# 2020can_master_v4_x.net
KiCad netlist of a schematic drawn in EAGLE
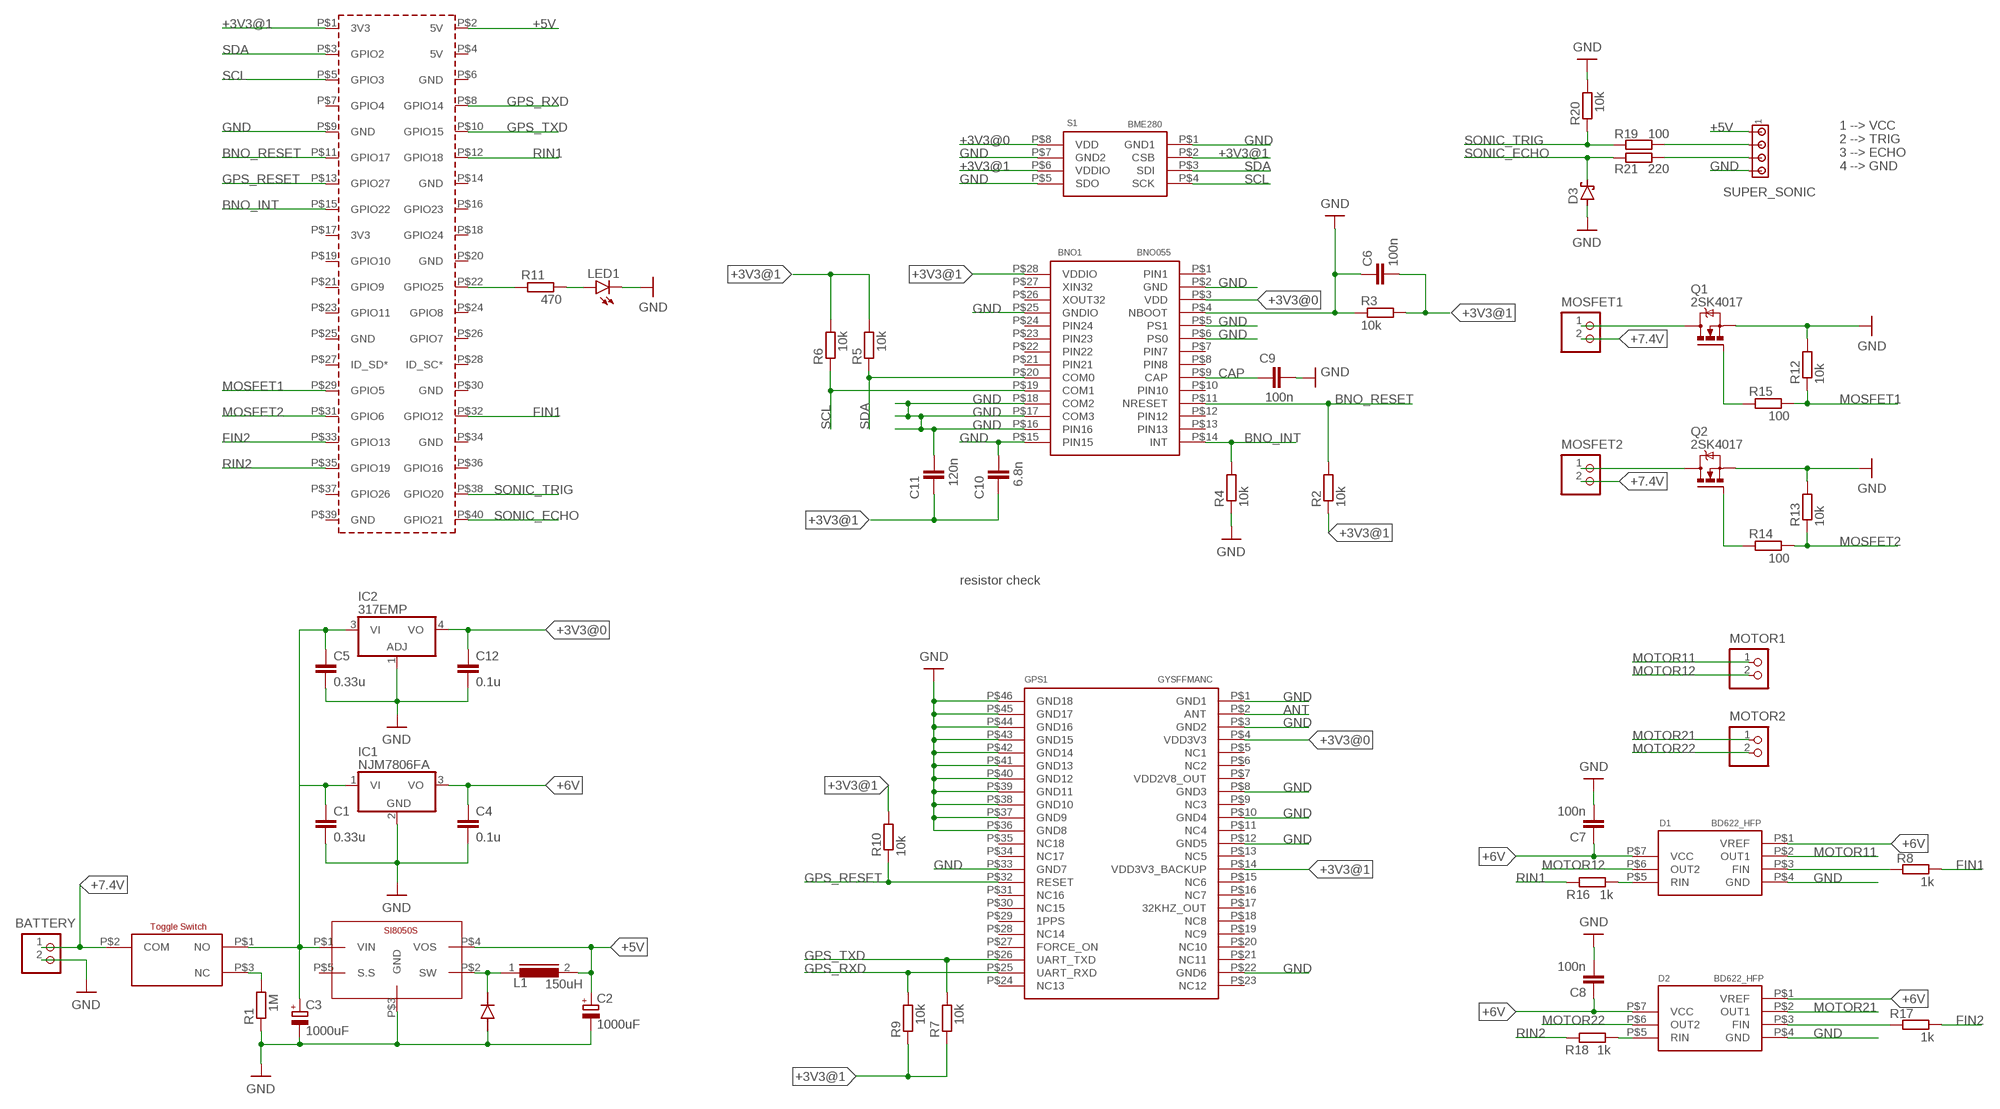
[diagram p0: schematic, sheet 1]

(export (version "E")
  (design (tool "Eeschema 10.0.6"))
  (components
    (comp (ref "BATTERY")
      (value "B2P-VH")
      (footprint "eagle-import:B2P-VH")
      (libsource (lib "eagle-import") (part "B2P-VH"))
    )
    (comp (ref "BNO1")
      (value "BNO055")
      (footprint "eagle-import:BNO055")
      (libsource (lib "eagle-import") (part "BNO055"))
    )
    (comp (ref "C1")
      (value "0.33u")
      (footprint "eagle-import:C5B3")
      (libsource (lib "eagle-import") (part "C5/3"))
    )
    (comp (ref "C2")
      (value "1000uF")
      (footprint "eagle-import:E5-10,5")
      (libsource (lib "eagle-import") (part "CPOL-EUE5-10.5"))
    )
    (comp (ref "C3")
      (value "1000uF")
      (footprint "eagle-import:E5-10,5")
      (libsource (lib "eagle-import") (part "CPOL-EUE5-10.5"))
    )
    (comp (ref "C4")
      (value "0.1u")
      (footprint "eagle-import:C5B3")
      (libsource (lib "eagle-import") (part "C5/3"))
    )
    (comp (ref "C5")
      (value "0.33u")
      (footprint "eagle-import:C5B3")
      (libsource (lib "eagle-import") (part "C5/3"))
    )
    (comp (ref "C6")
      (value "100n")
      (footprint "eagle-import:C1206")
      (libsource (lib "eagle-import") (part "C-EUC1206"))
    )
    (comp (ref "C7")
      (value "100n")
      (footprint "eagle-import:C1206")
      (libsource (lib "eagle-import") (part "C-EUC1206"))
    )
    (comp (ref "C8")
      (value "100n")
      (footprint "eagle-import:C1206")
      (libsource (lib "eagle-import") (part "C-EUC1206"))
    )
    (comp (ref "C9")
      (value "100n")
      (footprint "eagle-import:C1206")
      (libsource (lib "eagle-import") (part "C-EUC1206"))
    )
    (comp (ref "C10")
      (value "6.8n")
      (footprint "eagle-import:C1206")
      (libsource (lib "eagle-import") (part "C-EUC1206"))
    )
    (comp (ref "C11")
      (value "120n")
      (footprint "eagle-import:C1206")
      (libsource (lib "eagle-import") (part "C-EUC1206"))
    )
    (comp (ref "C12")
      (value "0.1u")
      (footprint "eagle-import:C5B3")
      (libsource (lib "eagle-import") (part "C5/3"))
    )
    (comp (ref "D1")
      (value "BD622_HFP")
      (footprint "eagle-import:BD62___HRP7")
      (libsource (lib "eagle-import") (part "BD622_HFP"))
    )
    (comp (ref "D2")
      (value "BD622_HFP")
      (footprint "eagle-import:BD62___HRP7")
      (libsource (lib "eagle-import") (part "BD622_HFP"))
    )
    (comp (ref "D3")
      (value "15KEXXD")
      (footprint "eagle-import:DO201T15")
      (libsource (lib "eagle-import") (part "15KEXXD"))
    )
    (comp (ref "DIODE_1.1")
      (value "DIODE_1.5")
      (footprint "eagle-import:DIODE_1.5")
      (libsource (lib "eagle-import") (part "DIODE_1.5"))
    )
    (comp (ref "GPS1")
      (value "GYSFFMANC")
      (footprint "eagle-import:GYSFFMANC")
      (libsource (lib "eagle-import") (part "GYSFFMANC"))
    )
    (comp (ref "IC1")
      (value "NJM7806FA")
      (footprint "eagle-import:TO220V")
      (libsource (lib "eagle-import") (part "78TV6"))
    )
    (comp (ref "IC2")
      (value "317EMP")
      (footprint "eagle-import:SOT223")
      (libsource (lib "eagle-import") (part "317EMP"))
    )
    (comp (ref "L1")
      (value "150uH")
      (footprint "eagle-import:SFT830D")
      (libsource (lib "eagle-import") (part "SFT830D"))
    )
    (comp (ref "LED1")
      (value "LED5MM")
      (footprint "eagle-import:LED5MM")
      (libsource (lib "eagle-import") (part "LED5MM"))
    )
    (comp (ref "MOSFET1")
      (value "B2P-VH")
      (footprint "eagle-import:B2P-VH")
      (libsource (lib "eagle-import") (part "B2P-VH"))
    )
    (comp (ref "MOSFET2")
      (value "B2P-VH")
      (footprint "eagle-import:B2P-VH")
      (libsource (lib "eagle-import") (part "B2P-VH"))
    )
    (comp (ref "MOTOR1")
      (value "B2P-VH")
      (footprint "eagle-import:B2P-VH")
      (libsource (lib "eagle-import") (part "B2P-VH"))
    )
    (comp (ref "MOTOR2")
      (value "B2P-VH")
      (footprint "eagle-import:B2P-VH")
      (libsource (lib "eagle-import") (part "B2P-VH"))
    )
    (comp (ref "PCB1")
      (value "RPI3RPI3")
      (footprint "eagle-import:RPI3")
      (libsource (lib "eagle-import") (part "RPI3RPI3"))
    )
    (comp (ref "Q1")
      (value "2SK4017")
      (footprint "eagle-import:TO220BV")
      (libsource (lib "eagle-import") (part "IRF520"))
    )
    (comp (ref "Q2")
      (value "2SK4017")
      (footprint "eagle-import:TO220BV")
      (libsource (lib "eagle-import") (part "IRF520"))
    )
    (comp (ref "R1")
      (value "1M")
      (footprint "eagle-import:R1206")
      (libsource (lib "eagle-import") (part "R-EU_R1206"))
    )
    (comp (ref "R2")
      (value "10k")
      (footprint "eagle-import:R1206")
      (libsource (lib "eagle-import") (part "R-EU_R1206"))
    )
    (comp (ref "R3")
      (value "10k")
      (footprint "eagle-import:R1206")
      (libsource (lib "eagle-import") (part "R-EU_R1206"))
    )
    (comp (ref "R4")
      (value "10k")
      (footprint "eagle-import:R1206")
      (libsource (lib "eagle-import") (part "R-EU_R1206"))
    )
    (comp (ref "R5")
      (value "10k")
      (footprint "eagle-import:R1206")
      (libsource (lib "eagle-import") (part "R-EU_R1206"))
    )
    (comp (ref "R6")
      (value "10k")
      (footprint "eagle-import:R1206")
      (libsource (lib "eagle-import") (part "R-EU_R1206"))
    )
    (comp (ref "R7")
      (value "10k")
      (footprint "eagle-import:R1206")
      (libsource (lib "eagle-import") (part "R-EU_R1206"))
    )
    (comp (ref "R8")
      (value "1k")
      (footprint "eagle-import:R1206")
      (libsource (lib "eagle-import") (part "R-EU_R1206"))
    )
    (comp (ref "R9")
      (value "10k")
      (footprint "eagle-import:R1206")
      (libsource (lib "eagle-import") (part "R-EU_R1206"))
    )
    (comp (ref "R10")
      (value "10k")
      (footprint "eagle-import:R1206")
      (libsource (lib "eagle-import") (part "R-EU_R1206"))
    )
    (comp (ref "R11")
      (value "470")
      (footprint "eagle-import:0207_10")
      (libsource (lib "eagle-import") (part "R-EU_0207/10"))
    )
    (comp (ref "R12")
      (value "10k")
      (footprint "eagle-import:R1206")
      (libsource (lib "eagle-import") (part "R-EU_R1206"))
    )
    (comp (ref "R13")
      (value "10k")
      (footprint "eagle-import:R1206")
      (libsource (lib "eagle-import") (part "R-EU_R1206"))
    )
    (comp (ref "R14")
      (value "100")
      (footprint "eagle-import:0207_10")
      (libsource (lib "eagle-import") (part "R-EU_0207/10"))
    )
    (comp (ref "R15")
      (value "100")
      (footprint "eagle-import:0207_10")
      (libsource (lib "eagle-import") (part "R-EU_0207/10"))
    )
    (comp (ref "R16")
      (value "1k")
      (footprint "eagle-import:R1206")
      (libsource (lib "eagle-import") (part "R-EU_R1206"))
    )
    (comp (ref "R17")
      (value "1k")
      (footprint "eagle-import:R1206")
      (libsource (lib "eagle-import") (part "R-EU_R1206"))
    )
    (comp (ref "R18")
      (value "1k")
      (footprint "eagle-import:R1206")
      (libsource (lib "eagle-import") (part "R-EU_R1206"))
    )
    (comp (ref "R19")
      (value "100")
      (footprint "eagle-import:0207_10")
      (libsource (lib "eagle-import") (part "R-EU_0207/10"))
    )
    (comp (ref "R20")
      (value "10k")
      (footprint "eagle-import:R1206")
      (libsource (lib "eagle-import") (part "R-EU_R1206"))
    )
    (comp (ref "R21")
      (value "220")
      (footprint "eagle-import:0207_10")
      (libsource (lib "eagle-import") (part "R-EU_0207/10"))
    )
    (comp (ref "S1")
      (value "BME280")
      (footprint "eagle-import:BME280")
      (libsource (lib "eagle-import") (part "BME280"))
    )
    (comp (ref "SI8050S1")
      (value "SI8050S")
      (footprint "eagle-import:SI8050S")
      (libsource (lib "eagle-import") (part "SI8050S"))
    )
    (comp (ref "SUPER_SONIC")
      (value "MTA04-100")
      (footprint "eagle-import:10X04MTA")
      (libsource (lib "eagle-import") (part "MTA04-100"))
    )
    (comp (ref "SWITCH_2MS1T2B4M2QES1")
      (value "SWITCH_2MS1T2B4M2QES")
      (footprint "eagle-import:SWITCH_2MS1T2B4M2QES")
      (libsource (lib "eagle-import") (part "SWITCH_2MS1T2B4M2QES"))
    )
  )
  (nets
    (net (code "1") (name "+3V3@0") (class "Default")
      (node (ref "BNO1") (pin "P$3") (pinfunction "VDD_P$3") (pintype "bidirectional"))
      (node (ref "C12") (pin "1") (pinfunction "1_1") (pintype "passive"))
      (node (ref "GPS1") (pin "P$4") (pinfunction "VDD3V3_P$4") (pintype "bidirectional"))
      (node (ref "IC2") (pin "4") (pinfunction "VO_4") (pintype "passive"))
      (node (ref "S1") (pin "P$8") (pinfunction "VDD_P$8") (pintype "bidirectional"))
    )
    (net (code "2") (name "+3V3@1") (class "Default")
      (node (ref "BNO1") (pin "P$28") (pinfunction "VDDIO_P$28") (pintype "bidirectional"))
      (node (ref "C10") (pin "1") (pinfunction "1_1") (pintype "passive"))
      (node (ref "C11") (pin "1") (pinfunction "1_1") (pintype "passive"))
      (node (ref "C6") (pin "2") (pinfunction "2_2") (pintype "passive"))
      (node (ref "GPS1") (pin "P$14") (pinfunction "VDD3V3_BACKUP_P$14") (pintype "bidirectional"))
      (node (ref "PCB1") (pin "P$1") (pinfunction "3V3_P$1") (pintype "bidirectional"))
      (node (ref "R10") (pin "2") (pinfunction "2_2") (pintype "passive"))
      (node (ref "R2") (pin "1") (pinfunction "1_1") (pintype "passive"))
      (node (ref "R3") (pin "2") (pinfunction "2_2") (pintype "passive"))
      (node (ref "R5") (pin "2") (pinfunction "2_2") (pintype "passive"))
      (node (ref "R6") (pin "2") (pinfunction "2_2") (pintype "passive"))
      (node (ref "R7") (pin "1") (pinfunction "1_1") (pintype "passive"))
      (node (ref "R9") (pin "1") (pinfunction "1_1") (pintype "passive"))
      (node (ref "S1") (pin "P$2") (pinfunction "CSB_P$2") (pintype "bidirectional"))
      (node (ref "S1") (pin "P$6") (pinfunction "VDDIO_P$6") (pintype "bidirectional"))
    )
    (net (code "3") (name "+5V") (class "Default")
      (node (ref "C2") (pin "+") (pinfunction "+_+") (pintype "passive"))
      (node (ref "L1") (pin "2") (pinfunction "2_2") (pintype "passive"))
      (node (ref "PCB1") (pin "P$2") (pinfunction "5V_P$2") (pintype "bidirectional"))
      (node (ref "SI8050S1") (pin "P$4") (pinfunction "VOS_P$4") (pintype "bidirectional"))
      (node (ref "SUPER_SONIC") (pin "1") (pinfunction "1_1") (pintype "passive"))
    )
    (net (code "4") (name "+6V") (class "Default")
      (node (ref "C4") (pin "1") (pinfunction "1_1") (pintype "passive"))
      (node (ref "C7") (pin "1") (pinfunction "1_1") (pintype "passive"))
      (node (ref "C8") (pin "1") (pinfunction "1_1") (pintype "passive"))
      (node (ref "D1") (pin "P$1") (pinfunction "VREF_P$1") (pintype "bidirectional"))
      (node (ref "D1") (pin "P$7") (pinfunction "VCC_P$7") (pintype "bidirectional"))
      (node (ref "D2") (pin "P$1") (pinfunction "VREF_P$1") (pintype "bidirectional"))
      (node (ref "D2") (pin "P$7") (pinfunction "VCC_P$7") (pintype "bidirectional"))
      (node (ref "IC1") (pin "3") (pinfunction "VO_3") (pintype "passive"))
    )
    (net (code "5") (name "+7.4V") (class "Default")
      (node (ref "BATTERY") (pin "1") (pinfunction "1_1") (pintype "passive"))
      (node (ref "MOSFET1") (pin "2") (pinfunction "2_2") (pintype "passive"))
      (node (ref "MOSFET2") (pin "2") (pinfunction "2_2") (pintype "passive"))
      (node (ref "SWITCH_2MS1T2B4M2QES1") (pin "P$2") (pinfunction "COM_P$2") (pintype "bidirectional"))
    )
    (net (code "6") (name "/ANT") (class "Default")
      (node (ref "GPS1") (pin "P$2") (pinfunction "ANT_P$2") (pintype "bidirectional"))
    )
    (net (code "7") (name "/BNO_INT") (class "Default")
      (node (ref "BNO1") (pin "P$14") (pinfunction "INT_P$14") (pintype "bidirectional"))
      (node (ref "PCB1") (pin "P$15") (pinfunction "GPIO22_P$15") (pintype "bidirectional"))
      (node (ref "R4") (pin "2") (pinfunction "2_2") (pintype "passive"))
    )
    (net (code "8") (name "/BNO_RESET") (class "Default")
      (node (ref "BNO1") (pin "P$11") (pinfunction "NRESET_P$11") (pintype "bidirectional"))
      (node (ref "PCB1") (pin "P$11") (pinfunction "GPIO17_P$11") (pintype "bidirectional"))
      (node (ref "R2") (pin "2") (pinfunction "2_2") (pintype "passive"))
    )
    (net (code "9") (name "/CAP") (class "Default")
      (node (ref "BNO1") (pin "P$9") (pinfunction "CAP_P$9") (pintype "bidirectional"))
      (node (ref "C9") (pin "1") (pinfunction "1_1") (pintype "passive"))
    )
    (net (code "10") (name "/FIN1") (class "Default")
      (node (ref "PCB1") (pin "P$32") (pinfunction "GPIO12_P$32") (pintype "bidirectional"))
      (node (ref "R8") (pin "1") (pinfunction "1_1") (pintype "passive"))
    )
    (net (code "11") (name "/FIN2") (class "Default")
      (node (ref "PCB1") (pin "P$33") (pinfunction "GPIO13_P$33") (pintype "bidirectional"))
      (node (ref "R17") (pin "1") (pinfunction "1_1") (pintype "passive"))
    )
    (net (code "12") (name "/GPS_RESET") (class "Default")
      (node (ref "GPS1") (pin "P$32") (pinfunction "RESET_P$32") (pintype "bidirectional"))
      (node (ref "PCB1") (pin "P$13") (pinfunction "GPIO27_P$13") (pintype "bidirectional"))
      (node (ref "R10") (pin "1") (pinfunction "1_1") (pintype "passive"))
    )
    (net (code "13") (name "/GPS_RXD") (class "Default")
      (node (ref "GPS1") (pin "P$25") (pinfunction "UART_RXD_P$25") (pintype "bidirectional"))
      (node (ref "PCB1") (pin "P$8") (pinfunction "GPIO14_P$8") (pintype "bidirectional"))
      (node (ref "R9") (pin "2") (pinfunction "2_2") (pintype "passive"))
    )
    (net (code "14") (name "/GPS_TXD") (class "Default")
      (node (ref "GPS1") (pin "P$26") (pinfunction "UART_TXD_P$26") (pintype "bidirectional"))
      (node (ref "PCB1") (pin "P$10") (pinfunction "GPIO15_P$10") (pintype "bidirectional"))
      (node (ref "R7") (pin "2") (pinfunction "2_2") (pintype "passive"))
    )
    (net (code "15") (name "/MOSFET1") (class "Default")
      (node (ref "PCB1") (pin "P$29") (pinfunction "GPIO5_P$29") (pintype "bidirectional"))
      (node (ref "R12") (pin "1") (pinfunction "1_1") (pintype "passive"))
      (node (ref "R15") (pin "2") (pinfunction "2_2") (pintype "passive"))
    )
    (net (code "16") (name "/MOSFET2") (class "Default")
      (node (ref "PCB1") (pin "P$31") (pinfunction "GPIO6_P$31") (pintype "bidirectional"))
      (node (ref "R13") (pin "1") (pinfunction "1_1") (pintype "passive"))
      (node (ref "R14") (pin "2") (pinfunction "2_2") (pintype "passive"))
    )
    (net (code "17") (name "/MOTOR11") (class "Default")
      (node (ref "D1") (pin "P$2") (pinfunction "OUT1_P$2") (pintype "bidirectional"))
      (node (ref "MOTOR1") (pin "1") (pinfunction "1_1") (pintype "passive"))
    )
    (net (code "18") (name "/MOTOR12") (class "Default")
      (node (ref "D1") (pin "P$6") (pinfunction "OUT2_P$6") (pintype "bidirectional"))
      (node (ref "MOTOR1") (pin "2") (pinfunction "2_2") (pintype "passive"))
    )
    (net (code "19") (name "/MOTOR21") (class "Default")
      (node (ref "D2") (pin "P$2") (pinfunction "OUT1_P$2") (pintype "bidirectional"))
      (node (ref "MOTOR2") (pin "1") (pinfunction "1_1") (pintype "passive"))
    )
    (net (code "20") (name "/MOTOR22") (class "Default")
      (node (ref "D2") (pin "P$6") (pinfunction "OUT2_P$6") (pintype "bidirectional"))
      (node (ref "MOTOR2") (pin "2") (pinfunction "2_2") (pintype "passive"))
    )
    (net (code "21") (name "/RIN1") (class "Default")
      (node (ref "PCB1") (pin "P$12") (pinfunction "GPIO18_P$12") (pintype "bidirectional"))
      (node (ref "R16") (pin "2") (pinfunction "2_2") (pintype "passive"))
    )
    (net (code "22") (name "/RIN2") (class "Default")
      (node (ref "PCB1") (pin "P$35") (pinfunction "GPIO19_P$35") (pintype "bidirectional"))
      (node (ref "R18") (pin "2") (pinfunction "2_2") (pintype "passive"))
    )
    (net (code "23") (name "/SCL") (class "Default")
      (node (ref "BNO1") (pin "P$19") (pinfunction "COM1_P$19") (pintype "bidirectional"))
      (node (ref "PCB1") (pin "P$5") (pinfunction "GPIO3_P$5") (pintype "bidirectional"))
      (node (ref "R6") (pin "1") (pinfunction "1_1") (pintype "passive"))
      (node (ref "S1") (pin "P$4") (pinfunction "SCK_P$4") (pintype "bidirectional"))
    )
    (net (code "24") (name "/SDA") (class "Default")
      (node (ref "BNO1") (pin "P$20") (pinfunction "COM0_P$20") (pintype "bidirectional"))
      (node (ref "PCB1") (pin "P$3") (pinfunction "GPIO2_P$3") (pintype "bidirectional"))
      (node (ref "R5") (pin "1") (pinfunction "1_1") (pintype "passive"))
      (node (ref "S1") (pin "P$3") (pinfunction "SDI_P$3") (pintype "bidirectional"))
    )
    (net (code "25") (name "/SONIC_ECHO") (class "Default")
      (node (ref "D3") (pin "C") (pinfunction "C_C") (pintype "passive"))
      (node (ref "PCB1") (pin "P$40") (pinfunction "GPIO21_P$40") (pintype "bidirectional"))
      (node (ref "R21") (pin "1") (pinfunction "1_1") (pintype "passive"))
    )
    (net (code "26") (name "/SONIC_TRIG") (class "Default")
      (node (ref "PCB1") (pin "P$38") (pinfunction "GPIO20_P$38") (pintype "bidirectional"))
      (node (ref "R19") (pin "1") (pinfunction "1_1") (pintype "passive"))
      (node (ref "R20") (pin "1") (pinfunction "1_1") (pintype "passive"))
    )
    (net (code "27") (name "GND") (class "Default")
      (node (ref "BATTERY") (pin "2") (pinfunction "2_2") (pintype "passive"))
      (node (ref "BNO1") (pin "P$15") (pinfunction "PIN15_P$15") (pintype "bidirectional"))
      (node (ref "BNO1") (pin "P$16") (pinfunction "PIN16_P$16") (pintype "bidirectional"))
      (node (ref "BNO1") (pin "P$17") (pinfunction "COM3_P$17") (pintype "bidirectional"))
      (node (ref "BNO1") (pin "P$18") (pinfunction "COM2_P$18") (pintype "bidirectional"))
      (node (ref "BNO1") (pin "P$2") (pinfunction "GND_P$2") (pintype "bidirectional"))
      (node (ref "BNO1") (pin "P$25") (pinfunction "GNDIO_P$25") (pintype "bidirectional"))
      (node (ref "BNO1") (pin "P$4") (pinfunction "NBOOT_P$4") (pintype "bidirectional"))
      (node (ref "BNO1") (pin "P$5") (pinfunction "PS1_P$5") (pintype "bidirectional"))
      (node (ref "BNO1") (pin "P$6") (pinfunction "PS0_P$6") (pintype "bidirectional"))
      (node (ref "C1") (pin "2") (pinfunction "2_2") (pintype "passive"))
      (node (ref "C10") (pin "2") (pinfunction "2_2") (pintype "passive"))
      (node (ref "C11") (pin "2") (pinfunction "2_2") (pintype "passive"))
      (node (ref "C12") (pin "2") (pinfunction "2_2") (pintype "passive"))
      (node (ref "C2") (pin "-") (pinfunction "-_-") (pintype "passive"))
      (node (ref "C3") (pin "-") (pinfunction "-_-") (pintype "passive"))
      (node (ref "C4") (pin "2") (pinfunction "2_2") (pintype "passive"))
      (node (ref "C5") (pin "2") (pinfunction "2_2") (pintype "passive"))
      (node (ref "C6") (pin "1") (pinfunction "1_1") (pintype "passive"))
      (node (ref "C7") (pin "2") (pinfunction "2_2") (pintype "passive"))
      (node (ref "C8") (pin "2") (pinfunction "2_2") (pintype "passive"))
      (node (ref "C9") (pin "2") (pinfunction "2_2") (pintype "passive"))
      (node (ref "D1") (pin "P$4") (pinfunction "GND_P$4") (pintype "bidirectional"))
      (node (ref "D2") (pin "P$4") (pinfunction "GND_P$4") (pintype "bidirectional"))
      (node (ref "D3") (pin "A") (pinfunction "A_A") (pintype "passive"))
      (node (ref "DIODE_1.1") (pin "P$1") (pinfunction "ANODE_P$1") (pintype "bidirectional"))
      (node (ref "GPS1") (pin "P$1") (pinfunction "GND1_P$1") (pintype "bidirectional"))
      (node (ref "GPS1") (pin "P$10") (pinfunction "GND4_P$10") (pintype "bidirectional"))
      (node (ref "GPS1") (pin "P$12") (pinfunction "GND5_P$12") (pintype "bidirectional"))
      (node (ref "GPS1") (pin "P$22") (pinfunction "GND6_P$22") (pintype "bidirectional"))
      (node (ref "GPS1") (pin "P$3") (pinfunction "GND2_P$3") (pintype "bidirectional"))
      (node (ref "GPS1") (pin "P$33") (pinfunction "GND7_P$33") (pintype "bidirectional"))
      (node (ref "GPS1") (pin "P$36") (pinfunction "GND8_P$36") (pintype "bidirectional"))
      (node (ref "GPS1") (pin "P$37") (pinfunction "GND9_P$37") (pintype "bidirectional"))
      (node (ref "GPS1") (pin "P$38") (pinfunction "GND10_P$38") (pintype "bidirectional"))
      (node (ref "GPS1") (pin "P$39") (pinfunction "GND11_P$39") (pintype "bidirectional"))
      (node (ref "GPS1") (pin "P$40") (pinfunction "GND12_P$40") (pintype "bidirectional"))
      (node (ref "GPS1") (pin "P$41") (pinfunction "GND13_P$41") (pintype "bidirectional"))
      (node (ref "GPS1") (pin "P$42") (pinfunction "GND14_P$42") (pintype "bidirectional"))
      (node (ref "GPS1") (pin "P$43") (pinfunction "GND15_P$43") (pintype "bidirectional"))
      (node (ref "GPS1") (pin "P$44") (pinfunction "GND16_P$44") (pintype "bidirectional"))
      (node (ref "GPS1") (pin "P$45") (pinfunction "GND17_P$45") (pintype "bidirectional"))
      (node (ref "GPS1") (pin "P$46") (pinfunction "GND18_P$46") (pintype "bidirectional"))
      (node (ref "GPS1") (pin "P$8") (pinfunction "GND3_P$8") (pintype "bidirectional"))
      (node (ref "IC1") (pin "2") (pinfunction "GND_2") (pintype "passive"))
      (node (ref "IC2") (pin "1") (pinfunction "ADJ_1") (pintype "input"))
      (node (ref "LED1") (pin "K") (pinfunction "C_K") (pintype "passive"))
      (node (ref "PCB1") (pin "P$9") (pinfunction "GND_P$9") (pintype "bidirectional"))
      (node (ref "Q1") (pin "S") (pinfunction "S_S") (pintype "passive"))
      (node (ref "Q2") (pin "S") (pinfunction "S_S") (pintype "passive"))
      (node (ref "R1") (pin "1") (pinfunction "1_1") (pintype "passive"))
      (node (ref "R12") (pin "2") (pinfunction "2_2") (pintype "passive"))
      (node (ref "R13") (pin "2") (pinfunction "2_2") (pintype "passive"))
      (node (ref "R20") (pin "2") (pinfunction "2_2") (pintype "passive"))
      (node (ref "R3") (pin "1") (pinfunction "1_1") (pintype "passive"))
      (node (ref "R4") (pin "1") (pinfunction "1_1") (pintype "passive"))
      (node (ref "S1") (pin "P$1") (pinfunction "GND1_P$1") (pintype "bidirectional"))
      (node (ref "S1") (pin "P$5") (pinfunction "SDO_P$5") (pintype "bidirectional"))
      (node (ref "S1") (pin "P$7") (pinfunction "GND2_P$7") (pintype "bidirectional"))
      (node (ref "SI8050S1") (pin "P$3") (pinfunction "GND_P$3") (pintype "bidirectional"))
      (node (ref "SUPER_SONIC") (pin "4") (pinfunction "4_4") (pintype "passive"))
    )
    (net (code "28") (name "Net-(D1-FIN)") (class "Default")
      (node (ref "D1") (pin "P$3") (pinfunction "FIN_P$3") (pintype "bidirectional"))
      (node (ref "R8") (pin "2") (pinfunction "2_2") (pintype "passive"))
    )
    (net (code "29") (name "Net-(D1-RIN)") (class "Default")
      (node (ref "D1") (pin "P$5") (pinfunction "RIN_P$5") (pintype "bidirectional"))
      (node (ref "R16") (pin "1") (pinfunction "1_1") (pintype "passive"))
    )
    (net (code "30") (name "Net-(D2-FIN)") (class "Default")
      (node (ref "D2") (pin "P$3") (pinfunction "FIN_P$3") (pintype "bidirectional"))
      (node (ref "R17") (pin "2") (pinfunction "2_2") (pintype "passive"))
    )
    (net (code "31") (name "Net-(D2-RIN)") (class "Default")
      (node (ref "D2") (pin "P$5") (pinfunction "RIN_P$5") (pintype "bidirectional"))
      (node (ref "R18") (pin "1") (pinfunction "1_1") (pintype "passive"))
    )
    (net (code "32") (name "Net-(DIODE_1.1-CATHODE)") (class "Default")
      (node (ref "DIODE_1.1") (pin "P$2") (pinfunction "CATHODE_P$2") (pintype "bidirectional"))
      (node (ref "L1") (pin "1") (pinfunction "1_1") (pintype "passive"))
      (node (ref "SI8050S1") (pin "P$2") (pinfunction "SW_P$2") (pintype "bidirectional"))
    )
    (net (code "33") (name "Net-(IC1-VI)") (class "Default")
      (node (ref "C1") (pin "1") (pinfunction "1_1") (pintype "passive"))
      (node (ref "C3") (pin "+") (pinfunction "+_+") (pintype "passive"))
      (node (ref "C5") (pin "1") (pinfunction "1_1") (pintype "passive"))
      (node (ref "IC1") (pin "1") (pinfunction "VI_1") (pintype "input"))
      (node (ref "IC2") (pin "3") (pinfunction "VI_3") (pintype "input"))
      (node (ref "SI8050S1") (pin "P$1") (pinfunction "VIN_P$1") (pintype "bidirectional"))
      (node (ref "SWITCH_2MS1T2B4M2QES1") (pin "P$1") (pinfunction "NO_P$1") (pintype "bidirectional"))
    )
    (net (code "34") (name "Net-(LED1-PadA)") (class "Default")
      (node (ref "LED1") (pin "A") (pinfunction "A_A") (pintype "passive"))
      (node (ref "R11") (pin "2") (pinfunction "2_2") (pintype "passive"))
    )
    (net (code "35") (name "Net-(MOSFET1-Pad1)") (class "Default")
      (node (ref "MOSFET1") (pin "1") (pinfunction "1_1") (pintype "passive"))
      (node (ref "Q1") (pin "D") (pinfunction "D_D") (pintype "passive"))
    )
    (net (code "36") (name "Net-(MOSFET2-Pad1)") (class "Default")
      (node (ref "MOSFET2") (pin "1") (pinfunction "1_1") (pintype "passive"))
      (node (ref "Q2") (pin "D") (pinfunction "D_D") (pintype "passive"))
    )
    (net (code "37") (name "Net-(PCB1-GPIO25)") (class "Default")
      (node (ref "PCB1") (pin "P$22") (pinfunction "GPIO25_P$22") (pintype "bidirectional"))
      (node (ref "R11") (pin "1") (pinfunction "1_1") (pintype "passive"))
    )
    (net (code "38") (name "Net-(Q1-PadG)") (class "Default")
      (node (ref "Q1") (pin "G") (pinfunction "G_G") (pintype "passive"))
      (node (ref "R15") (pin "1") (pinfunction "1_1") (pintype "passive"))
    )
    (net (code "39") (name "Net-(Q2-PadG)") (class "Default")
      (node (ref "Q2") (pin "G") (pinfunction "G_G") (pintype "passive"))
      (node (ref "R14") (pin "1") (pinfunction "1_1") (pintype "passive"))
    )
    (net (code "40") (name "Net-(R19-Pad2)") (class "Default")
      (node (ref "R19") (pin "2") (pinfunction "2_2") (pintype "passive"))
      (node (ref "SUPER_SONIC") (pin "2") (pinfunction "2_2") (pintype "passive"))
    )
    (net (code "41") (name "Net-(R21-Pad2)") (class "Default")
      (node (ref "R21") (pin "2") (pinfunction "2_2") (pintype "passive"))
      (node (ref "SUPER_SONIC") (pin "3") (pinfunction "3_3") (pintype "passive"))
    )
    (net (code "42") (name "Net-(SWITCH_2MS1T2B4M2QES1-NC)") (class "Default")
      (node (ref "R1") (pin "2") (pinfunction "2_2") (pintype "passive"))
      (node (ref "SWITCH_2MS1T2B4M2QES1") (pin "P$3") (pinfunction "NC_P$3") (pintype "bidirectional"))
    )
    (net (code "43") (name "unconnected-(BNO1-PIN1-PadP$1)") (class "Default")
      (node (ref "BNO1") (pin "P$1") (pinfunction "PIN1_P$1") (pintype "bidirectional"))
    )
    (net (code "44") (name "unconnected-(BNO1-PIN7-PadP$7)") (class "Default")
      (node (ref "BNO1") (pin "P$7") (pinfunction "PIN7_P$7") (pintype "bidirectional"))
    )
    (net (code "45") (name "unconnected-(BNO1-PIN8-PadP$8)") (class "Default")
      (node (ref "BNO1") (pin "P$8") (pinfunction "PIN8_P$8") (pintype "bidirectional"))
    )
    (net (code "46") (name "unconnected-(BNO1-PIN10-PadP$10)") (class "Default")
      (node (ref "BNO1") (pin "P$10") (pinfunction "PIN10_P$10") (pintype "bidirectional"))
    )
    (net (code "47") (name "unconnected-(BNO1-PIN12-PadP$12)") (class "Default")
      (node (ref "BNO1") (pin "P$12") (pinfunction "PIN12_P$12") (pintype "bidirectional"))
    )
    (net (code "48") (name "unconnected-(BNO1-PIN13-PadP$13)") (class "Default")
      (node (ref "BNO1") (pin "P$13") (pinfunction "PIN13_P$13") (pintype "bidirectional"))
    )
    (net (code "49") (name "unconnected-(BNO1-PIN21-PadP$21)") (class "Default")
      (node (ref "BNO1") (pin "P$21") (pinfunction "PIN21_P$21") (pintype "bidirectional"))
    )
    (net (code "50") (name "unconnected-(BNO1-PIN22-PadP$22)") (class "Default")
      (node (ref "BNO1") (pin "P$22") (pinfunction "PIN22_P$22") (pintype "bidirectional"))
    )
    (net (code "51") (name "unconnected-(BNO1-PIN23-PadP$23)") (class "Default")
      (node (ref "BNO1") (pin "P$23") (pinfunction "PIN23_P$23") (pintype "bidirectional"))
    )
    (net (code "52") (name "unconnected-(BNO1-PIN24-PadP$24)") (class "Default")
      (node (ref "BNO1") (pin "P$24") (pinfunction "PIN24_P$24") (pintype "bidirectional"))
    )
    (net (code "53") (name "unconnected-(BNO1-XIN32-PadP$27)") (class "Default")
      (node (ref "BNO1") (pin "P$27") (pinfunction "XIN32_P$27") (pintype "bidirectional"))
    )
    (net (code "54") (name "unconnected-(BNO1-XOUT32-PadP$26)") (class "Default")
      (node (ref "BNO1") (pin "P$26") (pinfunction "XOUT32_P$26") (pintype "bidirectional"))
    )
    (net (code "55") (name "unconnected-(GPS1-1PPS-PadP$29)") (class "Default")
      (node (ref "GPS1") (pin "P$29") (pinfunction "1PPS_P$29") (pintype "bidirectional"))
    )
    (net (code "56") (name "unconnected-(GPS1-32KHZ_OUT-PadP$17)") (class "Default")
      (node (ref "GPS1") (pin "P$17") (pinfunction "32KHZ_OUT_P$17") (pintype "bidirectional"))
    )
    (net (code "57") (name "unconnected-(GPS1-FORCE_ON-PadP$27)") (class "Default")
      (node (ref "GPS1") (pin "P$27") (pinfunction "FORCE_ON_P$27") (pintype "bidirectional"))
    )
    (net (code "58") (name "unconnected-(GPS1-NC1-PadP$5)") (class "Default")
      (node (ref "GPS1") (pin "P$5") (pinfunction "NC1_P$5") (pintype "bidirectional"))
    )
    (net (code "59") (name "unconnected-(GPS1-NC2-PadP$6)") (class "Default")
      (node (ref "GPS1") (pin "P$6") (pinfunction "NC2_P$6") (pintype "bidirectional"))
    )
    (net (code "60") (name "unconnected-(GPS1-NC3-PadP$9)") (class "Default")
      (node (ref "GPS1") (pin "P$9") (pinfunction "NC3_P$9") (pintype "bidirectional"))
    )
    (net (code "61") (name "unconnected-(GPS1-NC4-PadP$11)") (class "Default")
      (node (ref "GPS1") (pin "P$11") (pinfunction "NC4_P$11") (pintype "bidirectional"))
    )
    (net (code "62") (name "unconnected-(GPS1-NC5-PadP$13)") (class "Default")
      (node (ref "GPS1") (pin "P$13") (pinfunction "NC5_P$13") (pintype "bidirectional"))
    )
    (net (code "63") (name "unconnected-(GPS1-NC6-PadP$15)") (class "Default")
      (node (ref "GPS1") (pin "P$15") (pinfunction "NC6_P$15") (pintype "bidirectional"))
    )
    (net (code "64") (name "unconnected-(GPS1-NC7-PadP$16)") (class "Default")
      (node (ref "GPS1") (pin "P$16") (pinfunction "NC7_P$16") (pintype "bidirectional"))
    )
    (net (code "65") (name "unconnected-(GPS1-NC8-PadP$18)") (class "Default")
      (node (ref "GPS1") (pin "P$18") (pinfunction "NC8_P$18") (pintype "bidirectional"))
    )
    (net (code "66") (name "unconnected-(GPS1-NC9-PadP$19)") (class "Default")
      (node (ref "GPS1") (pin "P$19") (pinfunction "NC9_P$19") (pintype "bidirectional"))
    )
    (net (code "67") (name "unconnected-(GPS1-NC10-PadP$20)") (class "Default")
      (node (ref "GPS1") (pin "P$20") (pinfunction "NC10_P$20") (pintype "bidirectional"))
    )
    (net (code "68") (name "unconnected-(GPS1-NC11-PadP$21)") (class "Default")
      (node (ref "GPS1") (pin "P$21") (pinfunction "NC11_P$21") (pintype "bidirectional"))
    )
    (net (code "69") (name "unconnected-(GPS1-NC12-PadP$23)") (class "Default")
      (node (ref "GPS1") (pin "P$23") (pinfunction "NC12_P$23") (pintype "bidirectional"))
    )
    (net (code "70") (name "unconnected-(GPS1-NC13-PadP$24)") (class "Default")
      (node (ref "GPS1") (pin "P$24") (pinfunction "NC13_P$24") (pintype "bidirectional"))
    )
    (net (code "71") (name "unconnected-(GPS1-NC14-PadP$28)") (class "Default")
      (node (ref "GPS1") (pin "P$28") (pinfunction "NC14_P$28") (pintype "bidirectional"))
    )
    (net (code "72") (name "unconnected-(GPS1-NC15-PadP$30)") (class "Default")
      (node (ref "GPS1") (pin "P$30") (pinfunction "NC15_P$30") (pintype "bidirectional"))
    )
    (net (code "73") (name "unconnected-(GPS1-NC16-PadP$31)") (class "Default")
      (node (ref "GPS1") (pin "P$31") (pinfunction "NC16_P$31") (pintype "bidirectional"))
    )
    (net (code "74") (name "unconnected-(GPS1-NC17-PadP$34)") (class "Default")
      (node (ref "GPS1") (pin "P$34") (pinfunction "NC17_P$34") (pintype "bidirectional"))
    )
    (net (code "75") (name "unconnected-(GPS1-NC18-PadP$35)") (class "Default")
      (node (ref "GPS1") (pin "P$35") (pinfunction "NC18_P$35") (pintype "bidirectional"))
    )
    (net (code "76") (name "unconnected-(GPS1-VDD2V8_OUT-PadP$7)") (class "Default")
      (node (ref "GPS1") (pin "P$7") (pinfunction "VDD2V8_OUT_P$7") (pintype "bidirectional"))
    )
    (net (code "77") (name "unconnected-(PCB1-3V3-PadP$17)") (class "Default")
      (node (ref "PCB1") (pin "P$17") (pinfunction "3V3_P$17") (pintype "bidirectional"))
    )
    (net (code "78") (name "unconnected-(PCB1-5V-PadP$4)") (class "Default")
      (node (ref "PCB1") (pin "P$4") (pinfunction "5V_P$4") (pintype "bidirectional"))
    )
    (net (code "79") (name "unconnected-(PCB1-GND-PadP$6)") (class "Default")
      (node (ref "PCB1") (pin "P$6") (pinfunction "GND_P$6") (pintype "bidirectional"))
    )
    (net (code "80") (name "unconnected-(PCB1-GND-PadP$14)") (class "Default")
      (node (ref "PCB1") (pin "P$14") (pinfunction "GND_P$14") (pintype "bidirectional"))
    )
    (net (code "81") (name "unconnected-(PCB1-GND-PadP$20)") (class "Default")
      (node (ref "PCB1") (pin "P$20") (pinfunction "GND_P$20") (pintype "bidirectional"))
    )
    (net (code "82") (name "unconnected-(PCB1-GND-PadP$25)") (class "Default")
      (node (ref "PCB1") (pin "P$25") (pinfunction "GND_P$25") (pintype "bidirectional"))
    )
    (net (code "83") (name "unconnected-(PCB1-GND-PadP$30)") (class "Default")
      (node (ref "PCB1") (pin "P$30") (pinfunction "GND_P$30") (pintype "bidirectional"))
    )
    (net (code "84") (name "unconnected-(PCB1-GND-PadP$34)") (class "Default")
      (node (ref "PCB1") (pin "P$34") (pinfunction "GND_P$34") (pintype "bidirectional"))
    )
    (net (code "85") (name "unconnected-(PCB1-GND-PadP$39)") (class "Default")
      (node (ref "PCB1") (pin "P$39") (pinfunction "GND_P$39") (pintype "bidirectional"))
    )
    (net (code "86") (name "unconnected-(PCB1-GPIO4-PadP$7)") (class "Default")
      (node (ref "PCB1") (pin "P$7") (pinfunction "GPIO4_P$7") (pintype "bidirectional"))
    )
    (net (code "87") (name "unconnected-(PCB1-GPIO7-PadP$26)") (class "Default")
      (node (ref "PCB1") (pin "P$26") (pinfunction "GPIO7_P$26") (pintype "bidirectional"))
    )
    (net (code "88") (name "unconnected-(PCB1-GPIO8-PadP$24)") (class "Default")
      (node (ref "PCB1") (pin "P$24") (pinfunction "GPIO8_P$24") (pintype "bidirectional"))
    )
    (net (code "89") (name "unconnected-(PCB1-GPIO9-PadP$21)") (class "Default")
      (node (ref "PCB1") (pin "P$21") (pinfunction "GPIO9_P$21") (pintype "bidirectional"))
    )
    (net (code "90") (name "unconnected-(PCB1-GPIO10-PadP$19)") (class "Default")
      (node (ref "PCB1") (pin "P$19") (pinfunction "GPIO10_P$19") (pintype "bidirectional"))
    )
    (net (code "91") (name "unconnected-(PCB1-GPIO11-PadP$23)") (class "Default")
      (node (ref "PCB1") (pin "P$23") (pinfunction "GPIO11_P$23") (pintype "bidirectional"))
    )
    (net (code "92") (name "unconnected-(PCB1-GPIO16-PadP$36)") (class "Default")
      (node (ref "PCB1") (pin "P$36") (pinfunction "GPIO16_P$36") (pintype "bidirectional"))
    )
    (net (code "93") (name "unconnected-(PCB1-GPIO23-PadP$16)") (class "Default")
      (node (ref "PCB1") (pin "P$16") (pinfunction "GPIO23_P$16") (pintype "bidirectional"))
    )
    (net (code "94") (name "unconnected-(PCB1-GPIO24-PadP$18)") (class "Default")
      (node (ref "PCB1") (pin "P$18") (pinfunction "GPIO24_P$18") (pintype "bidirectional"))
    )
    (net (code "95") (name "unconnected-(PCB1-GPIO26-PadP$37)") (class "Default")
      (node (ref "PCB1") (pin "P$37") (pinfunction "GPIO26_P$37") (pintype "bidirectional"))
    )
    (net (code "96") (name "unconnected-(PCB1-ID_SC*-PadP$28)") (class "Default")
      (node (ref "PCB1") (pin "P$28") (pinfunction "ID_SC*_P$28") (pintype "bidirectional"))
    )
    (net (code "97") (name "unconnected-(PCB1-ID_SD*-PadP$27)") (class "Default")
      (node (ref "PCB1") (pin "P$27") (pinfunction "ID_SD*_P$27") (pintype "bidirectional"))
    )
    (net (code "98") (name "unconnected-(SI8050S1-S.S-PadP$5)") (class "Default")
      (node (ref "SI8050S1") (pin "P$5") (pinfunction "S.S_P$5") (pintype "bidirectional"))
    )
  )
)
